# ROM_final_rev01.net
KiCad netlist of a schematic drawn in EAGLE
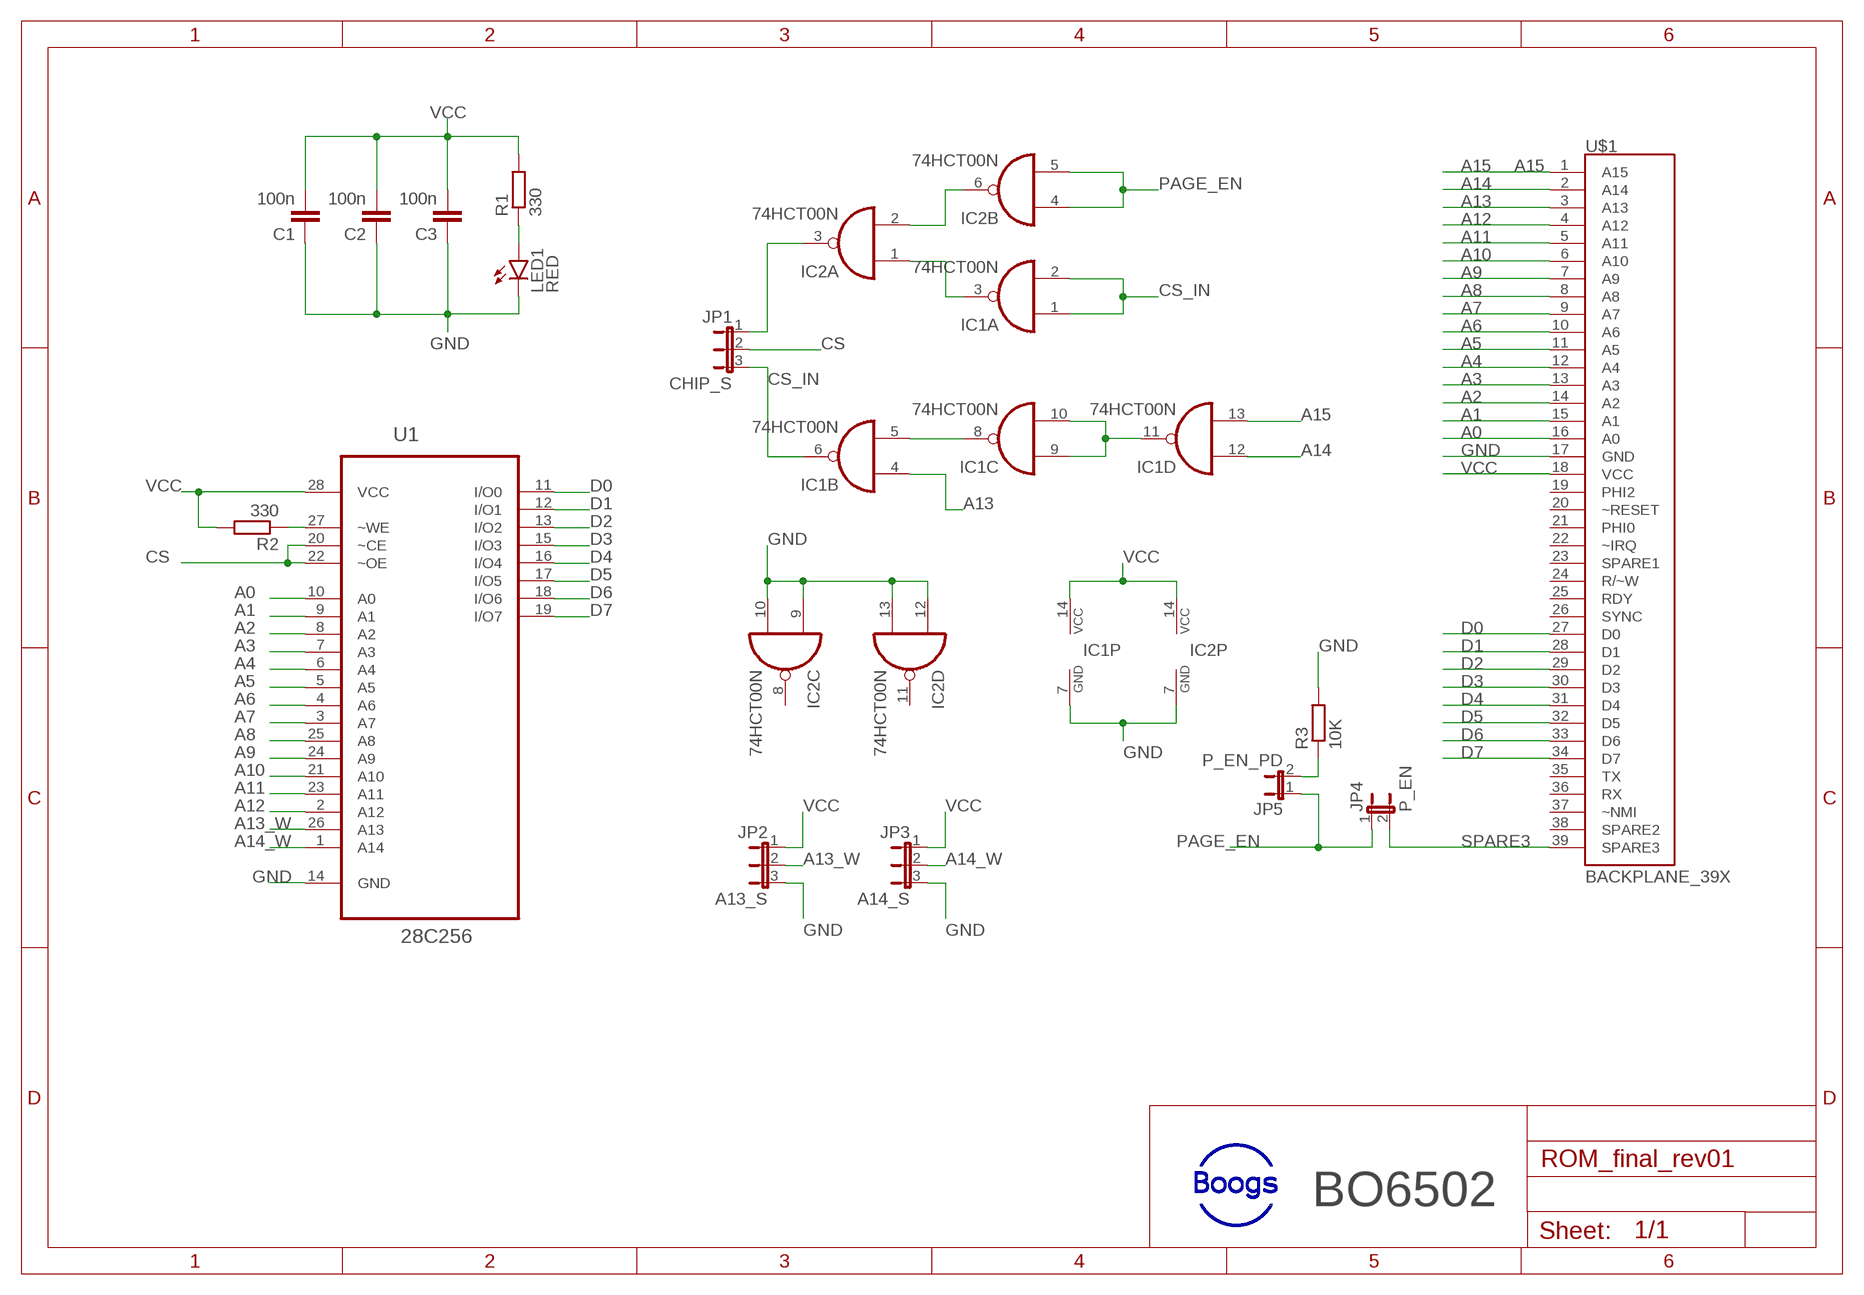
[diagram p0: schematic, sheet 1]

(export (version "E")
  (design (tool "Eeschema 10.0.6"))
  (components
    (comp (ref "C1")
      (value "100n")
      (footprint "eagle-import:C025-025X050")
      (libsource (lib "eagle-import") (part "C-EU025-025X050"))
    )
    (comp (ref "C2")
      (value "100n")
      (footprint "eagle-import:C025-025X050")
      (libsource (lib "eagle-import") (part "C-EU025-025X050"))
    )
    (comp (ref "C3")
      (value "100n")
      (footprint "eagle-import:C025-025X050")
      (libsource (lib "eagle-import") (part "C-EU025-025X050"))
    )
    (comp (ref "IC1")
      (value "74HCT00N")
      (footprint "eagle-import:DIL14")
      (libsource (lib "eagle-import") (part "7400NHCT"))
    )
    (comp (ref "IC2")
      (value "74HCT00N")
      (footprint "eagle-import:DIL14")
      (libsource (lib "eagle-import") (part "7400NHCT"))
    )
    (comp (ref "JP1")
      (value "CHIP_S")
      (footprint "eagle-import:JP2")
      (libsource (lib "eagle-import") (part "JP2E"))
    )
    (comp (ref "JP2")
      (value "A13_S")
      (footprint "eagle-import:JP2")
      (libsource (lib "eagle-import") (part "JP2E"))
    )
    (comp (ref "JP3")
      (value "A14_S")
      (footprint "eagle-import:JP2")
      (libsource (lib "eagle-import") (part "JP2E"))
    )
    (comp (ref "JP4")
      (value "P_EN")
      (footprint "eagle-import:JP1")
      (libsource (lib "eagle-import") (part "JP1E"))
    )
    (comp (ref "JP5")
      (value "P_EN_PD")
      (footprint "eagle-import:JP1")
      (libsource (lib "eagle-import") (part "JP1E"))
    )
    (comp (ref "LED1")
      (value "RED")
      (footprint "eagle-import:LED5MM")
      (libsource (lib "eagle-import") (part "LED5MM"))
    )
    (comp (ref "R1")
      (value "330")
      (footprint "eagle-import:0207_10")
      (libsource (lib "eagle-import") (part "R-EU_0207/10"))
    )
    (comp (ref "R2")
      (value "330")
      (footprint "eagle-import:0207_10")
      (libsource (lib "eagle-import") (part "R-EU_0207/10"))
    )
    (comp (ref "R3")
      (value "10K")
      (footprint "eagle-import:0207_10")
      (libsource (lib "eagle-import") (part "R-EU_0207/10"))
    )
    (comp (ref "U$1")
      (value "BACKPLANE_39X")
      (footprint "eagle-import:BP_39X")
      (fields (field (name "A15") "A15"))
      (libsource (lib "eagle-import") (part "BACKPLANE_39X"))
    )
    (comp (ref "U1")
      (value "28C256")
      (footprint "eagle-import:DIP254P1524X482-28")
      (fields (field (name "MF") "Microchip") (field (name "MP") "AT28C256-15PU"))
      (libsource (lib "eagle-import") (part "AT28C256-15PU"))
    )
  )
  (nets
    (net (code "1") (name "/A0") (class "Default")
      (node (ref "U$1") (pin "16") (pinfunction "A0_16") (pintype "bidirectional"))
      (node (ref "U1") (pin "10") (pinfunction "A0_10") (pintype "input"))
    )
    (net (code "2") (name "/A1") (class "Default")
      (node (ref "U$1") (pin "15") (pinfunction "A1_15") (pintype "bidirectional"))
      (node (ref "U1") (pin "9") (pinfunction "A1_9") (pintype "input"))
    )
    (net (code "3") (name "/A2") (class "Default")
      (node (ref "U$1") (pin "14") (pinfunction "A2_14") (pintype "bidirectional"))
      (node (ref "U1") (pin "8") (pinfunction "A2_8") (pintype "input"))
    )
    (net (code "4") (name "/A3") (class "Default")
      (node (ref "U$1") (pin "13") (pinfunction "A3_13") (pintype "bidirectional"))
      (node (ref "U1") (pin "7") (pinfunction "A3_7") (pintype "input"))
    )
    (net (code "5") (name "/A4") (class "Default")
      (node (ref "U$1") (pin "12") (pinfunction "A4_12") (pintype "bidirectional"))
      (node (ref "U1") (pin "6") (pinfunction "A4_6") (pintype "input"))
    )
    (net (code "6") (name "/A5") (class "Default")
      (node (ref "U$1") (pin "11") (pinfunction "A5_11") (pintype "bidirectional"))
      (node (ref "U1") (pin "5") (pinfunction "A5_5") (pintype "input"))
    )
    (net (code "7") (name "/A6") (class "Default")
      (node (ref "U$1") (pin "10") (pinfunction "A6_10") (pintype "bidirectional"))
      (node (ref "U1") (pin "4") (pinfunction "A6_4") (pintype "input"))
    )
    (net (code "8") (name "/A7") (class "Default")
      (node (ref "U$1") (pin "9") (pinfunction "A7_9") (pintype "bidirectional"))
      (node (ref "U1") (pin "3") (pinfunction "A7_3") (pintype "input"))
    )
    (net (code "9") (name "/A8") (class "Default")
      (node (ref "U$1") (pin "8") (pinfunction "A8_8") (pintype "bidirectional"))
      (node (ref "U1") (pin "25") (pinfunction "A8_25") (pintype "input"))
    )
    (net (code "10") (name "/A9") (class "Default")
      (node (ref "U$1") (pin "7") (pinfunction "A9_7") (pintype "bidirectional"))
      (node (ref "U1") (pin "24") (pinfunction "A9_24") (pintype "input"))
    )
    (net (code "11") (name "/A10") (class "Default")
      (node (ref "U$1") (pin "6") (pinfunction "A10_6") (pintype "bidirectional"))
      (node (ref "U1") (pin "21") (pinfunction "A10_21") (pintype "input"))
    )
    (net (code "12") (name "/A11") (class "Default")
      (node (ref "U$1") (pin "5") (pinfunction "A11_5") (pintype "bidirectional"))
      (node (ref "U1") (pin "23") (pinfunction "A11_23") (pintype "input"))
    )
    (net (code "13") (name "/A12") (class "Default")
      (node (ref "U$1") (pin "4") (pinfunction "A12_4") (pintype "bidirectional"))
      (node (ref "U1") (pin "2") (pinfunction "A12_2") (pintype "input"))
    )
    (net (code "14") (name "/A13") (class "Default")
      (node (ref "IC1") (pin "4") (pinfunction "I0_4") (pintype "input"))
      (node (ref "U$1") (pin "3") (pinfunction "A13_3") (pintype "bidirectional"))
    )
    (net (code "15") (name "/A13_W") (class "Default")
      (node (ref "JP2") (pin "2") (pinfunction "2_2") (pintype "passive"))
      (node (ref "U1") (pin "26") (pinfunction "A13_26") (pintype "input"))
    )
    (net (code "16") (name "/A14") (class "Default")
      (node (ref "IC1") (pin "12") (pinfunction "I0_12") (pintype "input"))
      (node (ref "U$1") (pin "2") (pinfunction "A14_2") (pintype "bidirectional"))
    )
    (net (code "17") (name "/A14_W") (class "Default")
      (node (ref "JP3") (pin "2") (pinfunction "2_2") (pintype "passive"))
      (node (ref "U1") (pin "1") (pinfunction "A14_1") (pintype "input"))
    )
    (net (code "18") (name "/A15") (class "Default")
      (node (ref "IC1") (pin "13") (pinfunction "I1_13") (pintype "input"))
      (node (ref "U$1") (pin "1") (pinfunction "A15_1") (pintype "bidirectional"))
    )
    (net (code "19") (name "/CS") (class "Default")
      (node (ref "JP1") (pin "2") (pinfunction "2_2") (pintype "passive"))
      (node (ref "U1") (pin "20") (pinfunction "~{CE}_20") (pintype "input"))
      (node (ref "U1") (pin "22") (pinfunction "~{OE}_22") (pintype "input"))
    )
    (net (code "20") (name "/CS_IN") (class "Default")
      (node (ref "IC1") (pin "1") (pinfunction "I0_1") (pintype "input"))
      (node (ref "IC1") (pin "2") (pinfunction "I1_2") (pintype "input"))
      (node (ref "IC1") (pin "6") (pinfunction "O_6") (pintype "output"))
      (node (ref "JP1") (pin "3") (pinfunction "3_3") (pintype "passive"))
    )
    (net (code "21") (name "/D0") (class "Default")
      (node (ref "U$1") (pin "27") (pinfunction "D0_27") (pintype "bidirectional"))
      (node (ref "U1") (pin "11") (pinfunction "I/O0_11") (pintype "bidirectional"))
    )
    (net (code "22") (name "/D1") (class "Default")
      (node (ref "U$1") (pin "28") (pinfunction "D1_28") (pintype "bidirectional"))
      (node (ref "U1") (pin "12") (pinfunction "I/O1_12") (pintype "bidirectional"))
    )
    (net (code "23") (name "/D2") (class "Default")
      (node (ref "U$1") (pin "29") (pinfunction "D2_29") (pintype "bidirectional"))
      (node (ref "U1") (pin "13") (pinfunction "I/O2_13") (pintype "bidirectional"))
    )
    (net (code "24") (name "/D3") (class "Default")
      (node (ref "U$1") (pin "30") (pinfunction "D3_30") (pintype "bidirectional"))
      (node (ref "U1") (pin "15") (pinfunction "I/O3_15") (pintype "bidirectional"))
    )
    (net (code "25") (name "/D4") (class "Default")
      (node (ref "U$1") (pin "31") (pinfunction "D4_31") (pintype "bidirectional"))
      (node (ref "U1") (pin "16") (pinfunction "I/O4_16") (pintype "bidirectional"))
    )
    (net (code "26") (name "/D5") (class "Default")
      (node (ref "U$1") (pin "32") (pinfunction "D5_32") (pintype "bidirectional"))
      (node (ref "U1") (pin "17") (pinfunction "I/O5_17") (pintype "bidirectional"))
    )
    (net (code "27") (name "/D6") (class "Default")
      (node (ref "U$1") (pin "33") (pinfunction "D6_33") (pintype "bidirectional"))
      (node (ref "U1") (pin "18") (pinfunction "I/O6_18") (pintype "bidirectional"))
    )
    (net (code "28") (name "/D7") (class "Default")
      (node (ref "U$1") (pin "34") (pinfunction "D7_34") (pintype "bidirectional"))
      (node (ref "U1") (pin "19") (pinfunction "I/O7_19") (pintype "bidirectional"))
    )
    (net (code "29") (name "/GND") (class "Default")
      (node (ref "C1") (pin "1") (pinfunction "1_1") (pintype "passive"))
      (node (ref "C2") (pin "1") (pinfunction "1_1") (pintype "passive"))
      (node (ref "C3") (pin "1") (pinfunction "1_1") (pintype "passive"))
      (node (ref "IC1") (pin "7") (pinfunction "GND_7") (pintype "power_in"))
      (node (ref "IC2") (pin "10") (pinfunction "I1_10") (pintype "input"))
      (node (ref "IC2") (pin "12") (pinfunction "I0_12") (pintype "input"))
      (node (ref "IC2") (pin "13") (pinfunction "I1_13") (pintype "input"))
      (node (ref "IC2") (pin "7") (pinfunction "GND_7") (pintype "power_in"))
      (node (ref "IC2") (pin "9") (pinfunction "I0_9") (pintype "input"))
      (node (ref "JP2") (pin "3") (pinfunction "3_3") (pintype "passive"))
      (node (ref "JP3") (pin "3") (pinfunction "3_3") (pintype "passive"))
      (node (ref "LED1") (pin "K") (pinfunction "C_K") (pintype "passive"))
      (node (ref "R3") (pin "2") (pinfunction "2_2") (pintype "passive"))
      (node (ref "U$1") (pin "17") (pinfunction "GND_17") (pintype "bidirectional"))
      (node (ref "U1") (pin "14") (pinfunction "GND_14") (pintype "passive"))
    )
    (net (code "30") (name "/PAGE_EN") (class "Default")
      (node (ref "IC2") (pin "4") (pinfunction "I0_4") (pintype "input"))
      (node (ref "IC2") (pin "5") (pinfunction "I1_5") (pintype "input"))
      (node (ref "JP4") (pin "1") (pinfunction "1_1") (pintype "passive"))
      (node (ref "JP5") (pin "1") (pinfunction "1_1") (pintype "passive"))
    )
    (net (code "31") (name "/SPARE3") (class "Default")
      (node (ref "JP4") (pin "2") (pinfunction "2_2") (pintype "passive"))
      (node (ref "U$1") (pin "39") (pinfunction "SPARE3_39") (pintype "bidirectional"))
    )
    (net (code "32") (name "/VCC") (class "Default")
      (node (ref "C1") (pin "2") (pinfunction "2_2") (pintype "passive"))
      (node (ref "C2") (pin "2") (pinfunction "2_2") (pintype "passive"))
      (node (ref "C3") (pin "2") (pinfunction "2_2") (pintype "passive"))
      (node (ref "IC1") (pin "14") (pinfunction "VCC_14") (pintype "power_in"))
      (node (ref "IC2") (pin "14") (pinfunction "VCC_14") (pintype "power_in"))
      (node (ref "JP2") (pin "1") (pinfunction "1_1") (pintype "passive"))
      (node (ref "JP3") (pin "1") (pinfunction "1_1") (pintype "passive"))
      (node (ref "R1") (pin "2") (pinfunction "2_2") (pintype "passive"))
      (node (ref "R2") (pin "2") (pinfunction "2_2") (pintype "passive"))
      (node (ref "U$1") (pin "18") (pinfunction "VCC_18") (pintype "bidirectional"))
      (node (ref "U1") (pin "28") (pinfunction "VCC_28") (pintype "power_in"))
    )
    (net (code "33") (name "Net-(IC1A-O)") (class "Default")
      (node (ref "IC1") (pin "3") (pinfunction "O_3") (pintype "output"))
      (node (ref "IC2") (pin "1") (pinfunction "I0_1") (pintype "input"))
    )
    (net (code "34") (name "Net-(IC1B-I1)") (class "Default")
      (node (ref "IC1") (pin "5") (pinfunction "I1_5") (pintype "input"))
      (node (ref "IC1") (pin "8") (pinfunction "O_8") (pintype "output"))
    )
    (net (code "35") (name "Net-(IC1C-I0)") (class "Default")
      (node (ref "IC1") (pin "10") (pinfunction "I1_10") (pintype "input"))
      (node (ref "IC1") (pin "11") (pinfunction "O_11") (pintype "output"))
      (node (ref "IC1") (pin "9") (pinfunction "I0_9") (pintype "input"))
    )
    (net (code "36") (name "Net-(IC2A-I1)") (class "Default")
      (node (ref "IC2") (pin "2") (pinfunction "I1_2") (pintype "input"))
      (node (ref "IC2") (pin "6") (pinfunction "O_6") (pintype "output"))
    )
    (net (code "37") (name "Net-(IC2A-O)") (class "Default")
      (node (ref "IC2") (pin "3") (pinfunction "O_3") (pintype "output"))
      (node (ref "JP1") (pin "1") (pinfunction "1_1") (pintype "passive"))
    )
    (net (code "38") (name "Net-(JP5-Pad2)") (class "Default")
      (node (ref "JP5") (pin "2") (pinfunction "2_2") (pintype "passive"))
      (node (ref "R3") (pin "1") (pinfunction "1_1") (pintype "passive"))
    )
    (net (code "39") (name "Net-(LED1-PadA)") (class "Default")
      (node (ref "LED1") (pin "A") (pinfunction "A_A") (pintype "passive"))
      (node (ref "R1") (pin "1") (pinfunction "1_1") (pintype "passive"))
    )
    (net (code "40") (name "Net-(U1-~{WE})") (class "Default")
      (node (ref "R2") (pin "1") (pinfunction "1_1") (pintype "passive"))
      (node (ref "U1") (pin "27") (pinfunction "~{WE}_27") (pintype "input"))
    )
    (net (code "41") (name "unconnected-(IC2C-O-Pad8)") (class "Default")
      (node (ref "IC2") (pin "8") (pinfunction "O_8") (pintype "output"))
    )
    (net (code "42") (name "unconnected-(IC2D-O-Pad11)") (class "Default")
      (node (ref "IC2") (pin "11") (pinfunction "O_11") (pintype "output"))
    )
    (net (code "43") (name "unconnected-(U$1-PHI0-Pad21)") (class "Default")
      (node (ref "U$1") (pin "21") (pinfunction "PHI0_21") (pintype "bidirectional"))
    )
    (net (code "44") (name "unconnected-(U$1-PHI2-Pad19)") (class "Default")
      (node (ref "U$1") (pin "19") (pinfunction "PHI2_19") (pintype "bidirectional"))
    )
    (net (code "45") (name "unconnected-(U$1-RDY-Pad25)") (class "Default")
      (node (ref "U$1") (pin "25") (pinfunction "RDY_25") (pintype "bidirectional"))
    )
    (net (code "46") (name "unconnected-(U$1-RX-Pad36)") (class "Default")
      (node (ref "U$1") (pin "36") (pinfunction "RX_36") (pintype "bidirectional"))
    )
    (net (code "47") (name "unconnected-(U$1-R{slash}~{W}-Pad24)") (class "Default")
      (node (ref "U$1") (pin "24") (pinfunction "R/~{W}_24") (pintype "bidirectional"))
    )
    (net (code "48") (name "unconnected-(U$1-SPARE1-Pad23)") (class "Default")
      (node (ref "U$1") (pin "23") (pinfunction "SPARE1_23") (pintype "bidirectional"))
    )
    (net (code "49") (name "unconnected-(U$1-SPARE2-Pad38)") (class "Default")
      (node (ref "U$1") (pin "38") (pinfunction "SPARE2_38") (pintype "bidirectional"))
    )
    (net (code "50") (name "unconnected-(U$1-SYNC-Pad26)") (class "Default")
      (node (ref "U$1") (pin "26") (pinfunction "SYNC_26") (pintype "bidirectional"))
    )
    (net (code "51") (name "unconnected-(U$1-TX-Pad35)") (class "Default")
      (node (ref "U$1") (pin "35") (pinfunction "TX_35") (pintype "bidirectional"))
    )
    (net (code "52") (name "unconnected-(U$1-~{IRQ}-Pad22)") (class "Default")
      (node (ref "U$1") (pin "22") (pinfunction "~{IRQ}_22") (pintype "bidirectional"))
    )
    (net (code "53") (name "unconnected-(U$1-~{NMI}-Pad37)") (class "Default")
      (node (ref "U$1") (pin "37") (pinfunction "~{NMI}_37") (pintype "bidirectional"))
    )
    (net (code "54") (name "unconnected-(U$1-~{RESET}-Pad20)") (class "Default")
      (node (ref "U$1") (pin "20") (pinfunction "~{RESET}_20") (pintype "bidirectional"))
    )
  )
)
